# RGB_ARRAY.net
KiCad netlist of a schematic drawn in Altium Designer
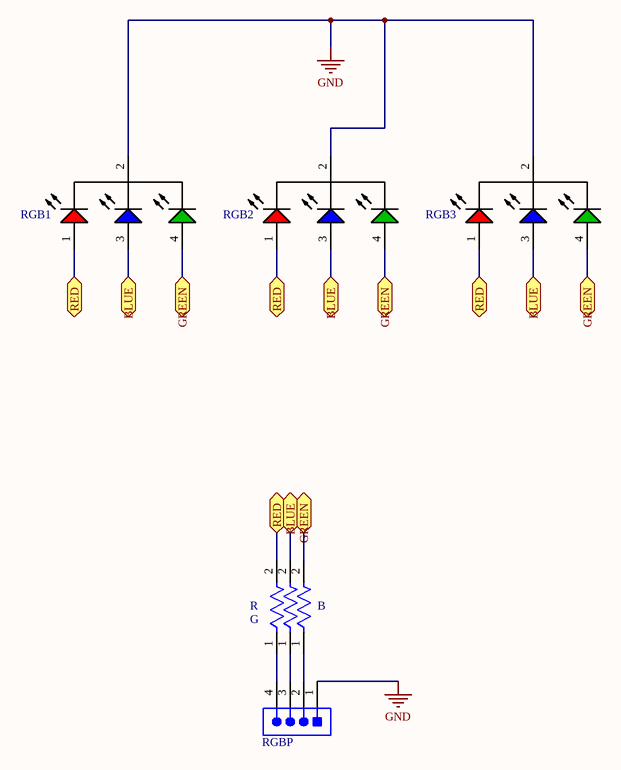
[diagram p0: RGB_ARRAY.SchDoc]

(export (version "E")
  (design (tool "Eeschema 10.0.6"))
  (components
    (comp (ref "B")
      (value "RNC55H1002FSB14")
      (footprint "FP-RNC55-MFG")
      (description "RES 10K OHM 1/8W 1% AXIAL")
      (fields
        (field (name "TOLERANCE") "1%")
        (field (name "OCTOPART") "https://octopart.com/rnc55h1002fs-vishay-40848808")
      )
      (libsource (lib "Altium Content Vault") (part "1029c3af85768c4190bb7ad29bc67b5"))
    )
    (comp (ref "G")
      (value "RNC55H1002FSB14")
      (footprint "FP-RNC55-MFG")
      (description "RES 10K OHM 1/8W 1% AXIAL")
      (fields
        (field (name "TOLERANCE") "1%")
        (field (name "OCTOPART") "https://octopart.com/rnc55h1002fs-vishay-40848808")
      )
      (libsource (lib "Altium Content Vault") (part "1029c3af85768c4190bb7ad29bc67b5"))
    )
    (comp (ref "R")
      (value "RNC55H1002FSB14")
      (footprint "FP-RNC55-MFG")
      (description "RES 10K OHM 1/8W 1% AXIAL")
      (fields
        (field (name "TOLERANCE") "1%")
        (field (name "OCTOPART") "https://octopart.com/rnc55h1002fs-vishay-40848808")
      )
      (libsource (lib "Altium Content Vault") (part "1029c3af85768c4190bb7ad29bc67b5"))
    )
    (comp (ref "RGB1")
      (value "WP154A4SUREQBFZGC")
      (footprint "KING-WP154A4SUREQBFZGC_V")
      (description "Full Color LED Lamp, Dominant Wavelength RGB 630 / 525 / 465 nm, -40 to 85 degC, 4-Pin THD, RoHS")
      (fields (field (name "MANUFACTURER") "Kingbright"))
      (libsource (lib "Altium Content Vault") (part "LED-RGB-AKAA-4"))
    )
    (comp (ref "RGB2")
      (value "WP154A4SUREQBFZGC")
      (footprint "KING-WP154A4SUREQBFZGC_V")
      (description "Full Color LED Lamp, Dominant Wavelength RGB 630 / 525 / 465 nm, -40 to 85 degC, 4-Pin THD, RoHS")
      (fields (field (name "MANUFACTURER") "Kingbright"))
      (libsource (lib "Altium Content Vault") (part "LED-RGB-AKAA-4"))
    )
    (comp (ref "RGB3")
      (value "WP154A4SUREQBFZGC")
      (footprint "KING-WP154A4SUREQBFZGC_V")
      (description "Full Color LED Lamp, Dominant Wavelength RGB 630 / 525 / 465 nm, -40 to 85 degC, 4-Pin THD, RoHS")
      (fields (field (name "MANUFACTURER") "Kingbright"))
      (libsource (lib "Altium Content Vault") (part "LED-RGB-AKAA-4"))
    )
    (comp (ref "RGBP")
      (value "GRPB041VWVN-RC")
      (footprint "SLIN-GRPB041VWVN-RC_V")
      (fields (field (name "MANUFACTURER") "Sullins"))
      (libsource (lib "Altium Content Vault") (part "CN-1P-M-R4"))
    )
  )
  (nets
    (net (code "1") (name "/BLUE") (class "Default")
      (node (ref "G") (pin "2") (pinfunction "2_2") (pintype "passive"))
      (node (ref "RGB1") (pin "3") (pinfunction "BLUE_3") (pintype "passive"))
      (node (ref "RGB2") (pin "3") (pinfunction "BLUE_3") (pintype "passive"))
      (node (ref "RGB3") (pin "3") (pinfunction "BLUE_3") (pintype "passive"))
    )
    (net (code "2") (name "/GREEN") (class "Default")
      (node (ref "B") (pin "2") (pinfunction "2_2") (pintype "passive"))
      (node (ref "RGB1") (pin "4") (pinfunction "GREEN_4") (pintype "passive"))
      (node (ref "RGB2") (pin "4") (pinfunction "GREEN_4") (pintype "passive"))
      (node (ref "RGB3") (pin "4") (pinfunction "GREEN_4") (pintype "passive"))
    )
    (net (code "3") (name "/RED") (class "Default")
      (node (ref "R") (pin "2") (pinfunction "2_2") (pintype "passive"))
      (node (ref "RGB1") (pin "1") (pinfunction "RED_1") (pintype "passive"))
      (node (ref "RGB2") (pin "1") (pinfunction "RED_1") (pintype "passive"))
      (node (ref "RGB3") (pin "1") (pinfunction "RED_1") (pintype "passive"))
    )
    (net (code "4") (name "GND") (class "Default")
      (node (ref "RGB1") (pin "2") (pinfunction "CATHODE_2") (pintype "passive"))
      (node (ref "RGB2") (pin "2") (pinfunction "CATHODE_2") (pintype "passive"))
      (node (ref "RGB3") (pin "2") (pinfunction "CATHODE_2") (pintype "passive"))
      (node (ref "RGBP") (pin "1") (pinfunction "1_1") (pintype "passive"))
    )
    (net (code "5") (name "Net-(B-Pad1)") (class "Default")
      (node (ref "B") (pin "1") (pinfunction "1_1") (pintype "passive"))
      (node (ref "RGBP") (pin "2") (pinfunction "2_2") (pintype "passive"))
    )
    (net (code "6") (name "Net-(G-Pad1)") (class "Default")
      (node (ref "G") (pin "1") (pinfunction "1_1") (pintype "passive"))
      (node (ref "RGBP") (pin "3") (pinfunction "3_3") (pintype "passive"))
    )
    (net (code "7") (name "Net-(R-Pad1)") (class "Default")
      (node (ref "R") (pin "1") (pinfunction "1_1") (pintype "passive"))
      (node (ref "RGBP") (pin "4") (pinfunction "4_4") (pintype "passive"))
    )
  )
)
